# Due_Programmer.net
KiCad netlist of a schematic drawn in EAGLE
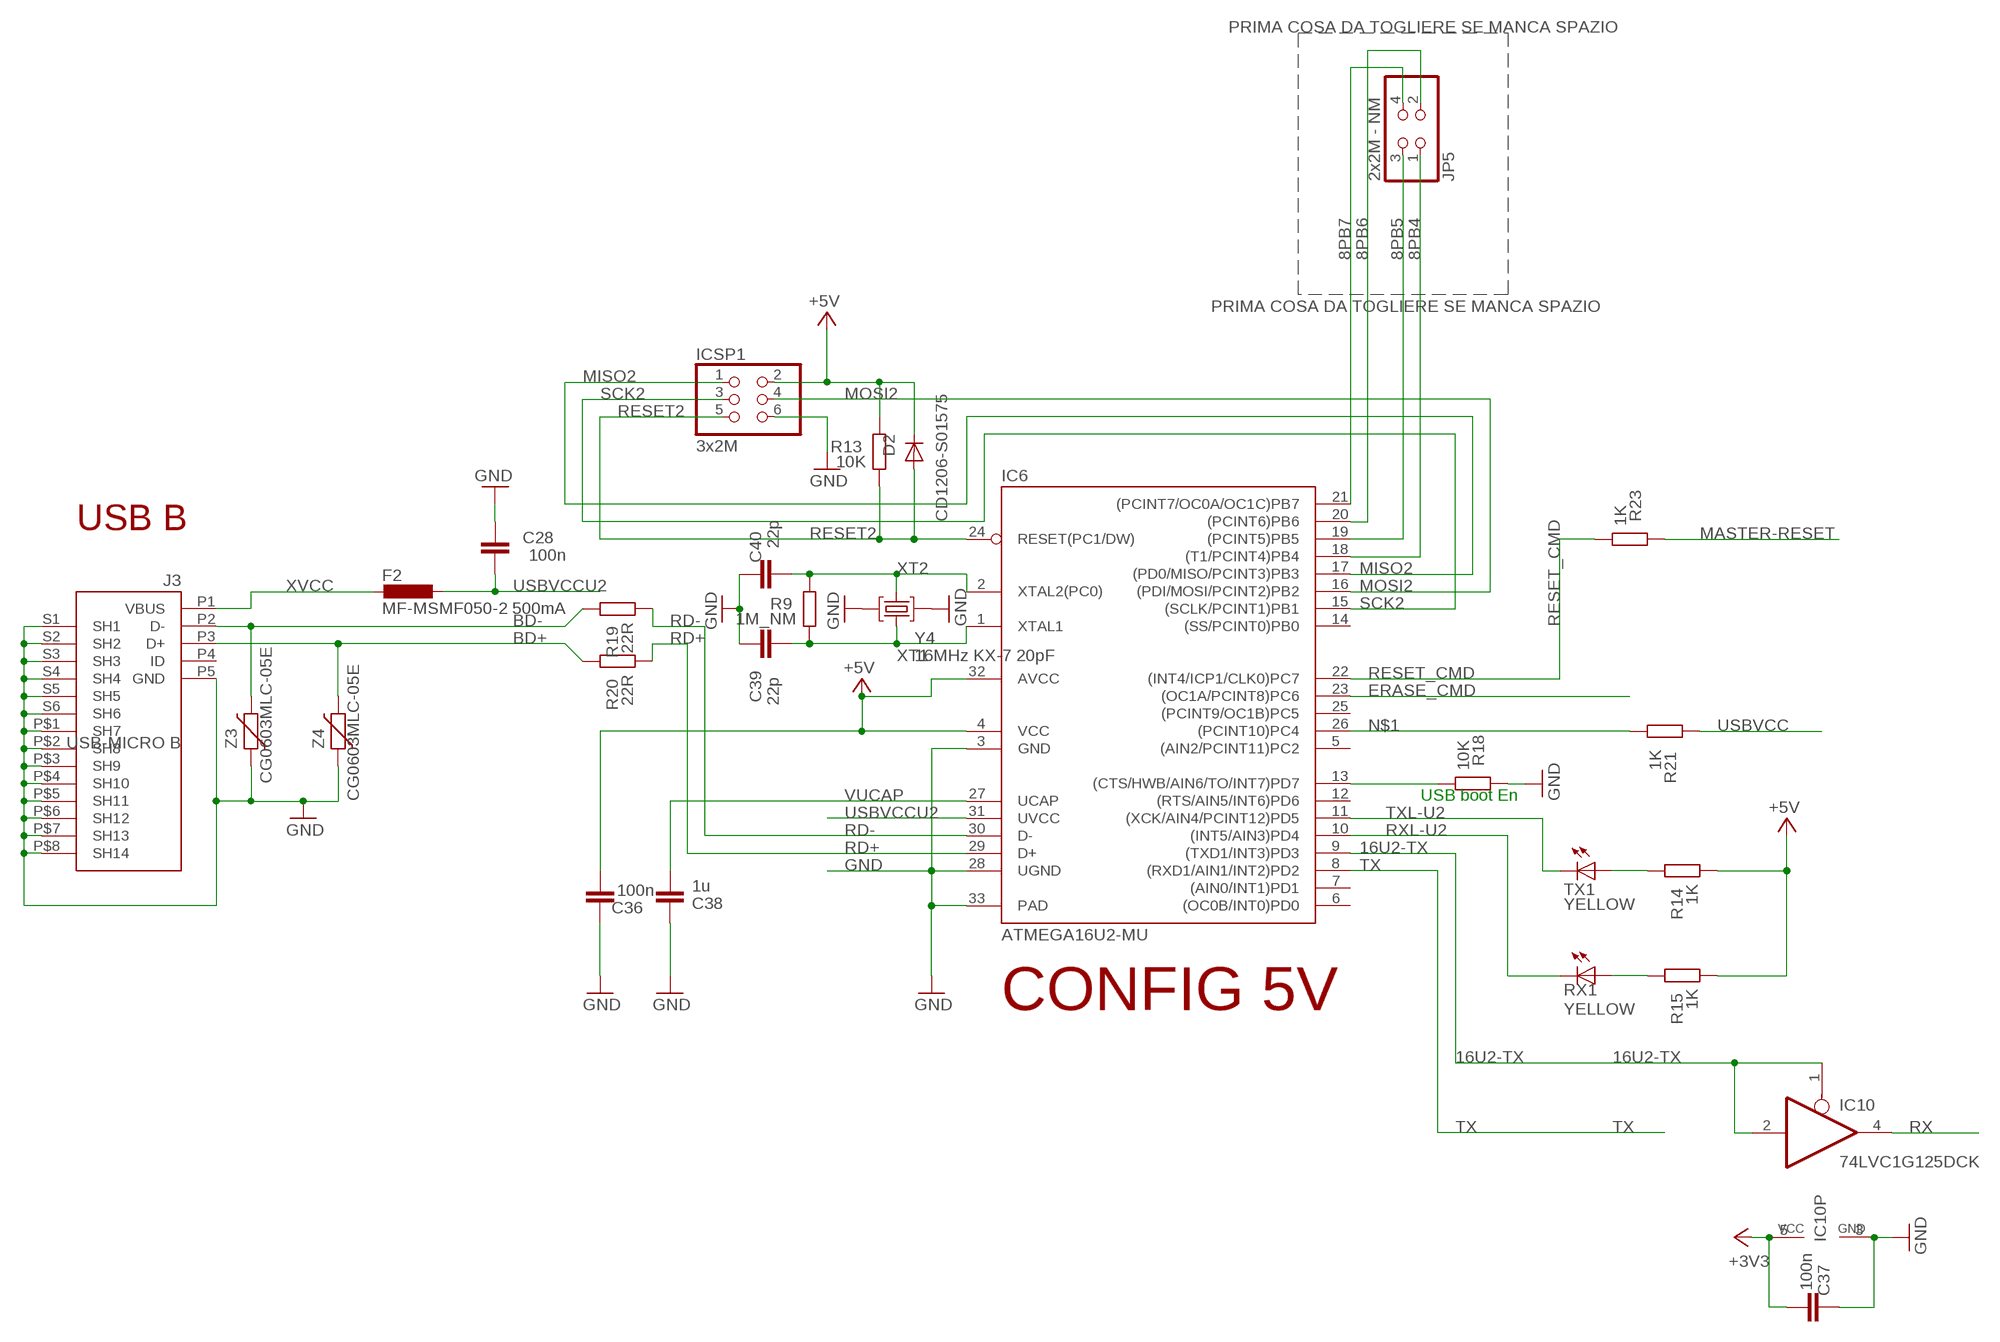
[diagram p0: schematic, sheet 1]

(export (version "E")
  (design (tool "Eeschema 10.0.6"))
  (components
    (comp (ref "C28")
      (value "100n")
      (footprint "eagle-import:C0402")
      (libsource (lib "eagle-import") (part "C-EUC0402"))
    )
    (comp (ref "C36")
      (value "100n")
      (footprint "eagle-import:C0402")
      (libsource (lib "eagle-import") (part "C-EUC0402"))
    )
    (comp (ref "C37")
      (value "100n")
      (footprint "eagle-import:C0402")
      (libsource (lib "eagle-import") (part "C-EUC0402"))
    )
    (comp (ref "C38")
      (value "1u")
      (footprint "eagle-import:C0402")
      (libsource (lib "eagle-import") (part "C-EUC0402"))
    )
    (comp (ref "C39")
      (value "22p")
      (footprint "eagle-import:C0402")
      (libsource (lib "eagle-import") (part "C-EUC0402"))
    )
    (comp (ref "C40")
      (value "22p")
      (footprint "eagle-import:C0402")
      (libsource (lib "eagle-import") (part "C-EUC0402"))
    )
    (comp (ref "D2")
      (value "CD1206-S01575")
      (footprint "eagle-import:MINIMELF")
      (libsource (lib "eagle-import") (part "DIODE-MINIMELF"))
    )
    (comp (ref "F2")
      (value "MF-MSMF050-2 500mA")
      (footprint "eagle-import:L1812")
      (libsource (lib "eagle-import") (part "L-EUL1812"))
    )
    (comp (ref "IC6")
      (value "ATMEGA16U2-MU")
      (footprint "eagle-import:MLF32")
      (libsource (lib "eagle-import") (part "ATMEGA16U2-MU"))
    )
    (comp (ref "IC10")
      (value "74LVC1G125DCK")
      (footprint "eagle-import:SC70-5")
      (libsource (lib "eagle-import") (part "741G125DCKLVC"))
    )
    (comp (ref "ICSP1")
      (value "3x2M")
      (footprint "eagle-import:2X03")
      (libsource (lib "eagle-import") (part "PINHD-2X3"))
    )
    (comp (ref "J3")
      (value "USB-MICRO B")
      (footprint "eagle-import:CON2_USB_MICRO_B_AT")
      (libsource (lib "eagle-import") (part "MYCON2_USB-MINI-B"))
    )
    (comp (ref "JP5")
      (value "2x2M - NM")
      (footprint "eagle-import:2X02")
      (libsource (lib "eagle-import") (part "PINHD-2X2"))
    )
    (comp (ref "R9")
      (value "1M_NM")
      (footprint "eagle-import:R0402")
      (libsource (lib "eagle-import") (part "R-EU_R0402"))
    )
    (comp (ref "R13")
      (value "10K")
      (footprint "eagle-import:R0402")
      (libsource (lib "eagle-import") (part "R-EU_R0402"))
    )
    (comp (ref "R14")
      (value "1K")
      (footprint "eagle-import:R0402")
      (libsource (lib "eagle-import") (part "R-EU_R0402"))
    )
    (comp (ref "R15")
      (value "1K")
      (footprint "eagle-import:R0402")
      (libsource (lib "eagle-import") (part "R-EU_R0402"))
    )
    (comp (ref "R18")
      (value "10K")
      (footprint "eagle-import:R0402")
      (libsource (lib "eagle-import") (part "R-EU_R0402"))
    )
    (comp (ref "R19")
      (value "22R")
      (footprint "eagle-import:R0402")
      (libsource (lib "eagle-import") (part "R-EU_R0402"))
    )
    (comp (ref "R20")
      (value "22R")
      (footprint "eagle-import:R0402")
      (libsource (lib "eagle-import") (part "R-EU_R0402"))
    )
    (comp (ref "R21")
      (value "1K")
      (footprint "eagle-import:R0402")
      (libsource (lib "eagle-import") (part "R-EU_R0402"))
    )
    (comp (ref "R23")
      (value "1K")
      (footprint "eagle-import:R0402")
      (libsource (lib "eagle-import") (part "R-EU_R0402"))
    )
    (comp (ref "RX1")
      (value "YELLOW")
      (footprint "eagle-import:CHIP-LED0805")
      (libsource (lib "eagle-import") (part "LEDCHIP-LED0805"))
    )
    (comp (ref "TX1")
      (value "YELLOW")
      (footprint "eagle-import:CHIP-LED0805")
      (libsource (lib "eagle-import") (part "LEDCHIP-LED0805"))
    )
    (comp (ref "Y4")
      (value "16MHz KX-7 20pF")
      (footprint "eagle-import:CRYSTAL-3.2-2.5")
      (libsource (lib "eagle-import") (part "CRYSTAL-3.2-2.5"))
    )
    (comp (ref "Z3")
      (value "CG0603MLC-05E")
      (footprint "eagle-import:CT_CN0603")
      (libsource (lib "eagle-import") (part "VARISTORCN0603"))
    )
    (comp (ref "Z4")
      (value "CG0603MLC-05E")
      (footprint "eagle-import:CT_CN0603")
      (libsource (lib "eagle-import") (part "VARISTORCN0603"))
    )
  )
  (nets
    (net (code "1") (name "+3V3") (class "Default")
      (node (ref "C37") (pin "1") (pinfunction "1_1") (pintype "passive"))
      (node (ref "IC10") (pin "5") (pinfunction "VCC_5") (pintype "power_in"))
    )
    (net (code "2") (name "+5V") (class "Default")
      (node (ref "C36") (pin "1") (pinfunction "1_1") (pintype "passive"))
      (node (ref "D2") (pin "C") (pinfunction "C_C") (pintype "passive"))
      (node (ref "IC6") (pin "32") (pinfunction "AVCC_32") (pintype "power_in"))
      (node (ref "IC6") (pin "4") (pinfunction "VCC_4") (pintype "power_in"))
      (node (ref "ICSP1") (pin "2") (pinfunction "2_2") (pintype "passive"))
      (node (ref "R13") (pin "2") (pinfunction "2_2") (pintype "passive"))
      (node (ref "R14") (pin "1") (pinfunction "1_1") (pintype "passive"))
      (node (ref "R15") (pin "1") (pinfunction "1_1") (pintype "passive"))
    )
    (net (code "3") (name "/8PB4") (class "Default")
      (node (ref "IC6") (pin "18") (pinfunction "(T1/PCINT4)PB4_18") (pintype "bidirectional"))
      (node (ref "JP5") (pin "1") (pinfunction "1_1") (pintype "passive"))
    )
    (net (code "4") (name "/8PB5") (class "Default")
      (node (ref "IC6") (pin "19") (pinfunction "(PCINT5)PB5_19") (pintype "bidirectional"))
      (node (ref "JP5") (pin "3") (pinfunction "3_3") (pintype "passive"))
    )
    (net (code "5") (name "/8PB6") (class "Default")
      (node (ref "IC6") (pin "20") (pinfunction "(PCINT6)PB6_20") (pintype "bidirectional"))
      (node (ref "JP5") (pin "2") (pinfunction "2_2") (pintype "passive"))
    )
    (net (code "6") (name "/8PB7") (class "Default")
      (node (ref "IC6") (pin "21") (pinfunction "(PCINT7/OC0A/OC1C)PB7_21") (pintype "bidirectional"))
      (node (ref "JP5") (pin "4") (pinfunction "4_4") (pintype "passive"))
    )
    (net (code "7") (name "/16U2-TX") (class "Default")
      (node (ref "IC10") (pin "1") (pinfunction "OE_1") (pintype "input"))
      (node (ref "IC10") (pin "2") (pinfunction "I_2") (pintype "input"))
      (node (ref "IC6") (pin "9") (pinfunction "(TXD1/INT3)PD3_9") (pintype "bidirectional"))
    )
    (net (code "8") (name "/BD+") (class "Default")
      (node (ref "J3") (pin "P3") (pinfunction "D+_P3") (pintype "bidirectional"))
      (node (ref "R20") (pin "2") (pinfunction "2_2") (pintype "passive"))
      (node (ref "Z4") (pin "2") (pinfunction "2_2") (pintype "passive"))
    )
    (net (code "9") (name "/BD-") (class "Default")
      (node (ref "J3") (pin "P2") (pinfunction "D-_P2") (pintype "bidirectional"))
      (node (ref "R19") (pin "2") (pinfunction "2_2") (pintype "passive"))
      (node (ref "Z3") (pin "2") (pinfunction "2_2") (pintype "passive"))
    )
    (net (code "10") (name "/ERASE_CMD") (class "Default")
      (node (ref "IC6") (pin "23") (pinfunction "(OC1A/PCINT8)PC6_23") (pintype "bidirectional"))
    )
    (net (code "11") (name "/MASTER-RESET") (class "Default")
      (node (ref "R23") (pin "2") (pinfunction "2_2") (pintype "passive"))
    )
    (net (code "12") (name "/MISO2") (class "Default")
      (node (ref "IC6") (pin "17") (pinfunction "(PD0/MISO/PCINT3)PB3_17") (pintype "bidirectional"))
      (node (ref "ICSP1") (pin "1") (pinfunction "1_1") (pintype "passive"))
    )
    (net (code "13") (name "/MOSI2") (class "Default")
      (node (ref "IC6") (pin "16") (pinfunction "(PDI/MOSI/PCINT2)PB2_16") (pintype "bidirectional"))
      (node (ref "ICSP1") (pin "4") (pinfunction "4_4") (pintype "passive"))
    )
    (net (code "14") (name "/N$1") (class "Default")
      (node (ref "IC6") (pin "26") (pinfunction "(PCINT10)PC4_26") (pintype "bidirectional"))
      (node (ref "R21") (pin "1") (pinfunction "1_1") (pintype "passive"))
    )
    (net (code "15") (name "/RD+") (class "Default")
      (node (ref "IC6") (pin "29") (pinfunction "D+_29") (pintype "bidirectional"))
      (node (ref "R20") (pin "1") (pinfunction "1_1") (pintype "passive"))
    )
    (net (code "16") (name "/RD-") (class "Default")
      (node (ref "IC6") (pin "30") (pinfunction "D-_30") (pintype "bidirectional"))
      (node (ref "R19") (pin "1") (pinfunction "1_1") (pintype "passive"))
    )
    (net (code "17") (name "/RESET2") (class "Default")
      (node (ref "D2") (pin "A") (pinfunction "A_A") (pintype "passive"))
      (node (ref "IC6") (pin "24") (pinfunction "RESET(PC1/DW)_24") (pintype "input"))
      (node (ref "ICSP1") (pin "5") (pinfunction "5_5") (pintype "passive"))
      (node (ref "R13") (pin "1") (pinfunction "1_1") (pintype "passive"))
    )
    (net (code "18") (name "/RESET_CMD") (class "Default")
      (node (ref "IC6") (pin "22") (pinfunction "(INT4/ICP1/CLK0)PC7_22") (pintype "bidirectional"))
      (node (ref "R23") (pin "1") (pinfunction "1_1") (pintype "passive"))
    )
    (net (code "19") (name "/RX") (class "Default")
      (node (ref "IC10") (pin "4") (pinfunction "O_4") (pintype "tri_state"))
    )
    (net (code "20") (name "/RXL-U2") (class "Default")
      (node (ref "IC6") (pin "10") (pinfunction "(INT5/AIN3)PD4_10") (pintype "bidirectional"))
      (node (ref "RX1") (pin "C") (pinfunction "C_C") (pintype "passive"))
    )
    (net (code "21") (name "/SCK2") (class "Default")
      (node (ref "IC6") (pin "15") (pinfunction "(SCLK/PCINT1)PB1_15") (pintype "bidirectional"))
      (node (ref "ICSP1") (pin "3") (pinfunction "3_3") (pintype "passive"))
    )
    (net (code "22") (name "/TX") (class "Default")
      (node (ref "IC6") (pin "8") (pinfunction "(RXD1/AIN1/INT2)PD2_8") (pintype "bidirectional"))
    )
    (net (code "23") (name "/TXL-U2") (class "Default")
      (node (ref "IC6") (pin "11") (pinfunction "(XCK/AIN4/PCINT12)PD5_11") (pintype "bidirectional"))
      (node (ref "TX1") (pin "C") (pinfunction "C_C") (pintype "passive"))
    )
    (net (code "24") (name "/USBVCC") (class "Default")
      (node (ref "R21") (pin "2") (pinfunction "2_2") (pintype "passive"))
    )
    (net (code "25") (name "/USBVCCU2") (class "Default")
      (node (ref "C28") (pin "1") (pinfunction "1_1") (pintype "passive"))
      (node (ref "F2") (pin "1") (pinfunction "1_1") (pintype "passive"))
      (node (ref "IC6") (pin "31") (pinfunction "UVCC_31") (pintype "power_in"))
    )
    (net (code "26") (name "/VUCAP") (class "Default")
      (node (ref "C38") (pin "1") (pinfunction "1_1") (pintype "passive"))
      (node (ref "IC6") (pin "27") (pinfunction "UCAP_27") (pintype "passive"))
    )
    (net (code "27") (name "/XT1") (class "Default")
      (node (ref "C39") (pin "1") (pinfunction "1_1") (pintype "passive"))
      (node (ref "IC6") (pin "1") (pinfunction "XTAL1_1") (pintype "bidirectional"))
      (node (ref "R9") (pin "1") (pinfunction "1_1") (pintype "passive"))
      (node (ref "Y4") (pin "1") (pinfunction "C1_1") (pintype "passive"))
    )
    (net (code "28") (name "/XT2") (class "Default")
      (node (ref "C40") (pin "1") (pinfunction "1_1") (pintype "passive"))
      (node (ref "IC6") (pin "2") (pinfunction "XTAL2(PC0)_2") (pintype "bidirectional"))
      (node (ref "R9") (pin "2") (pinfunction "2_2") (pintype "passive"))
      (node (ref "Y4") (pin "3") (pinfunction "C2_3") (pintype "passive"))
    )
    (net (code "29") (name "/XVCC") (class "Default")
      (node (ref "F2") (pin "2") (pinfunction "2_2") (pintype "passive"))
      (node (ref "J3") (pin "P1") (pinfunction "VBUS_P1") (pintype "power_in"))
    )
    (net (code "30") (name "GND") (class "Default")
      (node (ref "C28") (pin "2") (pinfunction "2_2") (pintype "passive"))
      (node (ref "C36") (pin "2") (pinfunction "2_2") (pintype "passive"))
      (node (ref "C37") (pin "2") (pinfunction "2_2") (pintype "passive"))
      (node (ref "C38") (pin "2") (pinfunction "2_2") (pintype "passive"))
      (node (ref "C39") (pin "2") (pinfunction "2_2") (pintype "passive"))
      (node (ref "C40") (pin "2") (pinfunction "2_2") (pintype "passive"))
      (node (ref "IC10") (pin "3") (pinfunction "GND_3") (pintype "power_in"))
      (node (ref "IC6") (pin "28") (pinfunction "UGND_28") (pintype "power_in"))
      (node (ref "IC6") (pin "3") (pinfunction "GND_3") (pintype "power_in"))
      (node (ref "IC6") (pin "33") (pinfunction "PAD_33") (pintype "power_in"))
      (node (ref "ICSP1") (pin "6") (pinfunction "6_6") (pintype "passive"))
      (node (ref "J3") (pin "P$1") (pinfunction "SH7_P$1") (pintype "passive"))
      (node (ref "J3") (pin "P$2") (pinfunction "SH8_P$2") (pintype "passive"))
      (node (ref "J3") (pin "P$3") (pinfunction "SH9_P$3") (pintype "passive"))
      (node (ref "J3") (pin "P$4") (pinfunction "SH10_P$4") (pintype "passive"))
      (node (ref "J3") (pin "P$5") (pinfunction "SH11_P$5") (pintype "passive"))
      (node (ref "J3") (pin "P$6") (pinfunction "SH12_P$6") (pintype "passive"))
      (node (ref "J3") (pin "P$7") (pinfunction "SH13_P$7") (pintype "passive"))
      (node (ref "J3") (pin "P$8") (pinfunction "SH14_P$8") (pintype "passive"))
      (node (ref "J3") (pin "P5") (pinfunction "GND_P5") (pintype "passive"))
      (node (ref "J3") (pin "S1") (pinfunction "SH1_S1") (pintype "passive"))
      (node (ref "J3") (pin "S2") (pinfunction "SH2_S2") (pintype "passive"))
      (node (ref "J3") (pin "S3") (pinfunction "SH3_S3") (pintype "passive"))
      (node (ref "J3") (pin "S4") (pinfunction "SH4_S4") (pintype "passive"))
      (node (ref "J3") (pin "S5") (pinfunction "SH5_S5") (pintype "passive"))
      (node (ref "J3") (pin "S6") (pinfunction "SH6_S6") (pintype "passive"))
      (node (ref "R18") (pin "2") (pinfunction "2_2") (pintype "passive"))
      (node (ref "Y4") (pin "2") (pinfunction "GND_2") (pintype "passive"))
      (node (ref "Y4") (pin "4") (pinfunction "GND_4") (pintype "passive"))
      (node (ref "Z3") (pin "1") (pinfunction "1_1") (pintype "passive"))
      (node (ref "Z4") (pin "1") (pinfunction "1_1") (pintype "passive"))
    )
    (net (code "31") (name "Net-(IC6-(CTS{slash}HWB{slash}AIN6{slash}TO{slash}INT7)PD7)") (class "Default")
      (node (ref "IC6") (pin "13") (pinfunction "(CTS/HWB/AIN6/TO/INT7)PD7_13") (pintype "bidirectional"))
      (node (ref "R18") (pin "1") (pinfunction "1_1") (pintype "passive"))
    )
    (net (code "32") (name "Net-(R14-Pad2)") (class "Default")
      (node (ref "R14") (pin "2") (pinfunction "2_2") (pintype "passive"))
      (node (ref "TX1") (pin "A") (pinfunction "A_A") (pintype "passive"))
    )
    (net (code "33") (name "Net-(R15-Pad2)") (class "Default")
      (node (ref "R15") (pin "2") (pinfunction "2_2") (pintype "passive"))
      (node (ref "RX1") (pin "A") (pinfunction "A_A") (pintype "passive"))
    )
    (net (code "34") (name "unconnected-(IC6-(AIN0{slash}INT1)PD1-Pad7)") (class "Default")
      (node (ref "IC6") (pin "7") (pinfunction "(AIN0/INT1)PD1_7") (pintype "bidirectional"))
    )
    (net (code "35") (name "unconnected-(IC6-(AIN2{slash}PCINT11)PC2-Pad5)") (class "Default")
      (node (ref "IC6") (pin "5") (pinfunction "(AIN2/PCINT11)PC2_5") (pintype "bidirectional"))
    )
    (net (code "36") (name "unconnected-(IC6-(OC0B{slash}INT0)PD0-Pad6)") (class "Default")
      (node (ref "IC6") (pin "6") (pinfunction "(OC0B/INT0)PD0_6") (pintype "bidirectional"))
    )
    (net (code "37") (name "unconnected-(IC6-(PCINT9{slash}OC1B)PC5-Pad25)") (class "Default")
      (node (ref "IC6") (pin "25") (pinfunction "(PCINT9/OC1B)PC5_25") (pintype "bidirectional"))
    )
    (net (code "38") (name "unconnected-(IC6-(RTS{slash}AIN5{slash}INT6)PD6-Pad12)") (class "Default")
      (node (ref "IC6") (pin "12") (pinfunction "(RTS/AIN5/INT6)PD6_12") (pintype "bidirectional"))
    )
    (net (code "39") (name "unconnected-(IC6-(SS{slash}PCINT0)PB0-Pad14)") (class "Default")
      (node (ref "IC6") (pin "14") (pinfunction "(SS/PCINT0)PB0_14") (pintype "bidirectional"))
    )
    (net (code "40") (name "unconnected-(J3-ID-PadP4)") (class "Default")
      (node (ref "J3") (pin "P4") (pinfunction "ID_P4") (pintype "bidirectional"))
    )
  )
)
